# SeismicPi.net
KiCad netlist of a schematic drawn in EAGLE
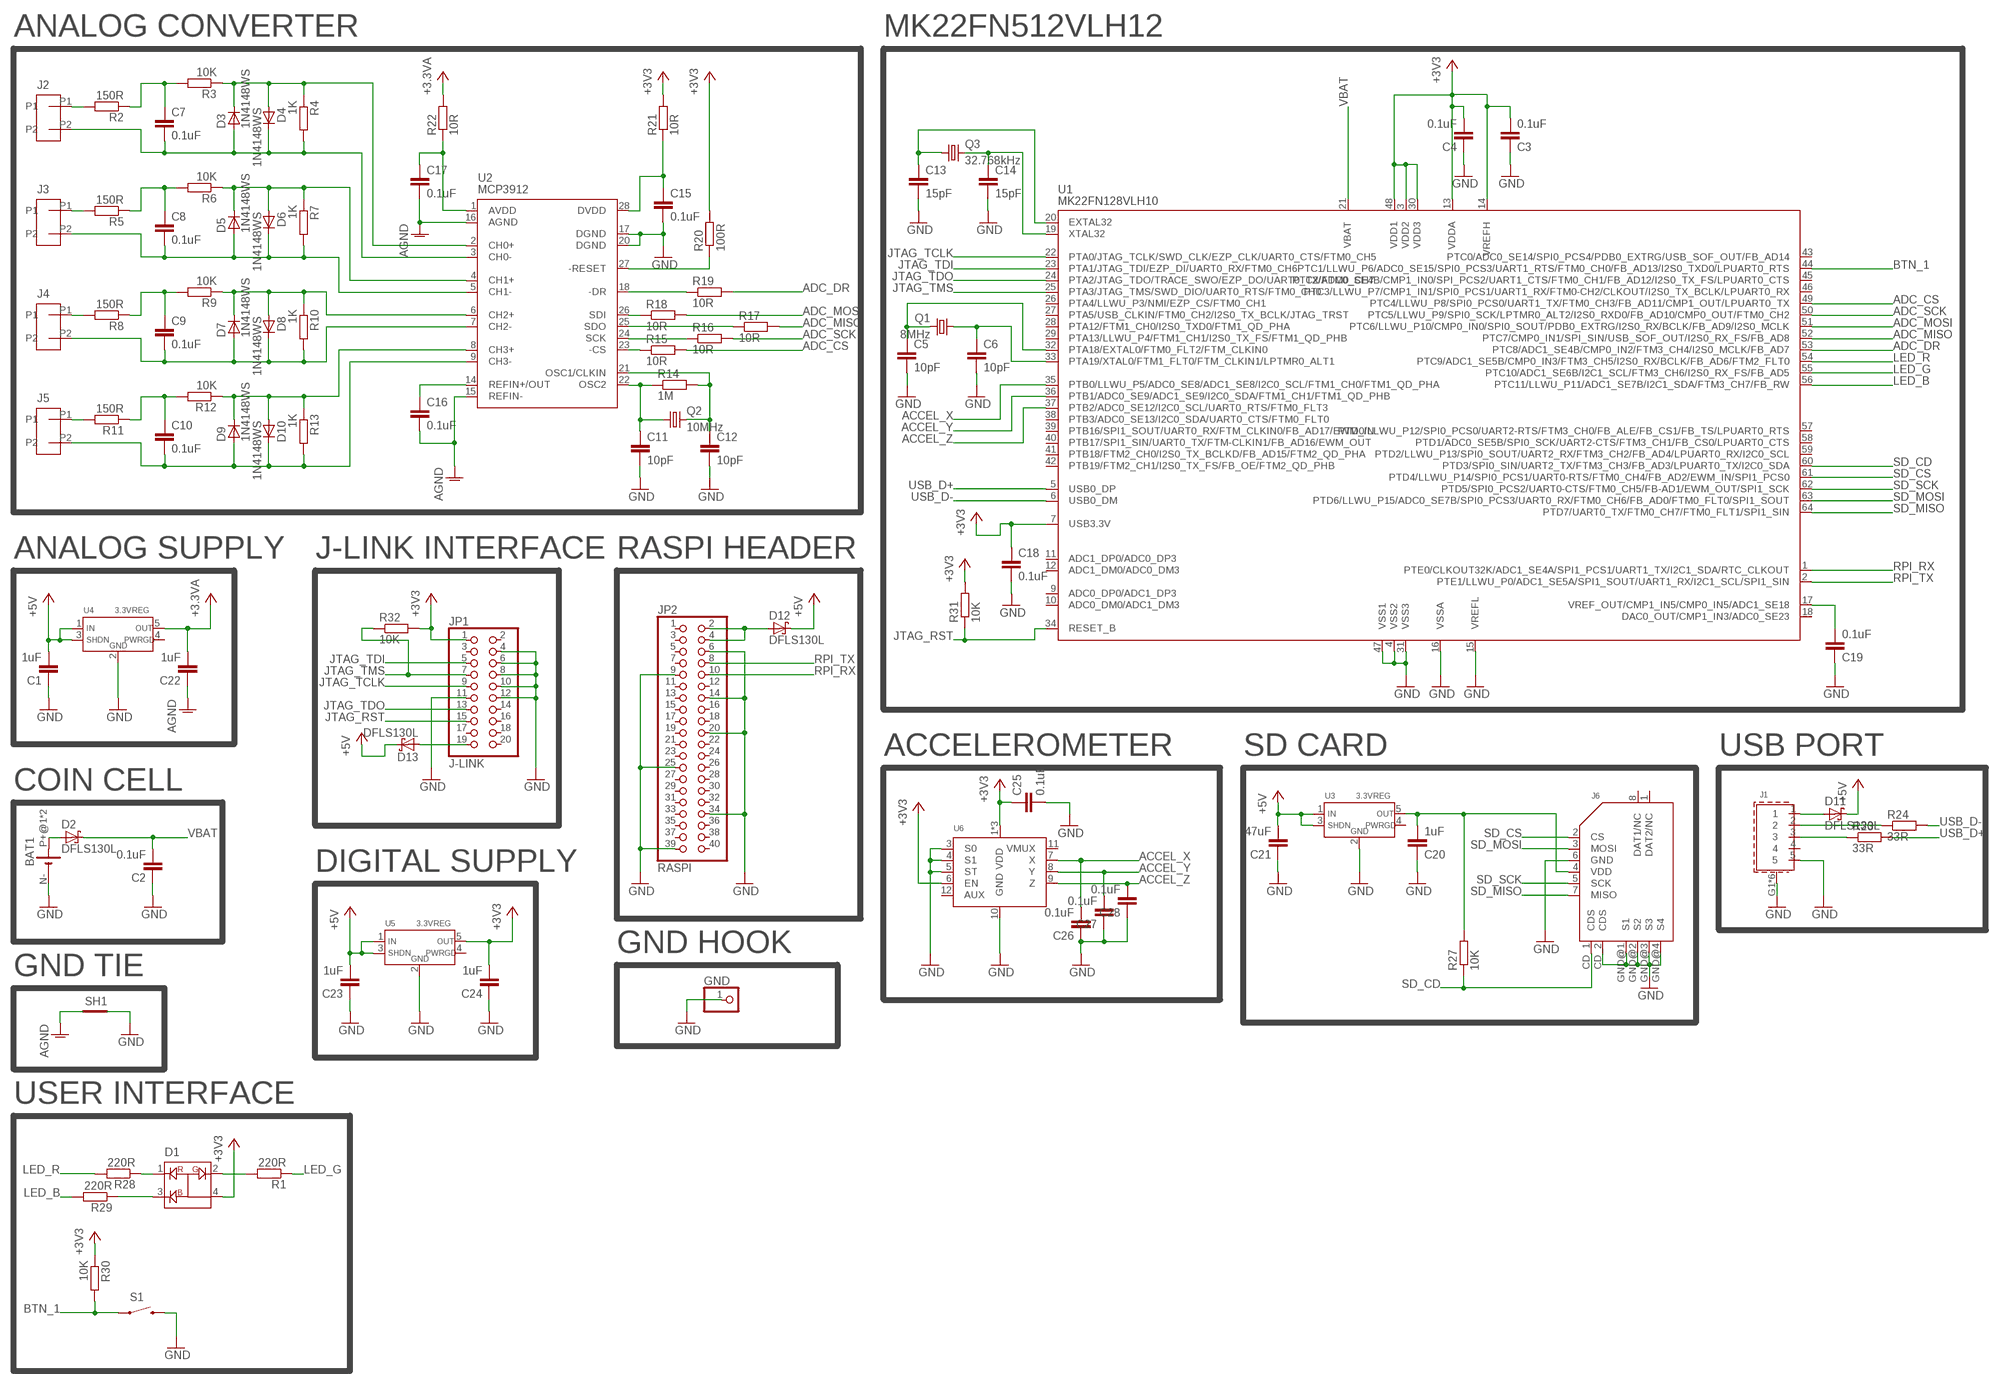
[diagram p0: schematic, sheet 1]

(export (version "E")
  (design (tool "Eeschema 10.0.6"))
  (components
    (comp (ref "BAT1")
      (value "BATTERY-HOLDER_11.6MM")
      (footprint "eagle-import:CELL_RETAINER_11.6MM")
      (fields (field (name "MF") "KEYSTONE") (field (name "MPN") "2997"))
      (libsource (lib "eagle-import") (part "BATTERY-HOLDER_11.6MM"))
    )
    (comp (ref "C1")
      (value "1uF")
      (footprint "eagle-import:C2012")
      (libsource (lib "eagle-import") (part "C-EUC2012"))
    )
    (comp (ref "C2")
      (value "0.1uF")
      (footprint "eagle-import:C2012")
      (libsource (lib "eagle-import") (part "C-EUC2012"))
    )
    (comp (ref "C3")
      (value "0.1uF")
      (footprint "eagle-import:C2012")
      (libsource (lib "eagle-import") (part "C-EUC2012"))
    )
    (comp (ref "C4")
      (value "0.1uF")
      (footprint "eagle-import:C2012")
      (libsource (lib "eagle-import") (part "C-EUC2012"))
    )
    (comp (ref "C5")
      (value "10pF")
      (footprint "eagle-import:C2012")
      (libsource (lib "eagle-import") (part "C-EUC2012"))
    )
    (comp (ref "C6")
      (value "10pF")
      (footprint "eagle-import:C2012")
      (libsource (lib "eagle-import") (part "C-EUC2012"))
    )
    (comp (ref "C7")
      (value "0.1uF")
      (footprint "eagle-import:C2012")
      (libsource (lib "eagle-import") (part "C-EUC2012"))
    )
    (comp (ref "C8")
      (value "0.1uF")
      (footprint "eagle-import:C2012")
      (libsource (lib "eagle-import") (part "C-EUC2012"))
    )
    (comp (ref "C9")
      (value "0.1uF")
      (footprint "eagle-import:C2012")
      (libsource (lib "eagle-import") (part "C-EUC2012"))
    )
    (comp (ref "C10")
      (value "0.1uF")
      (footprint "eagle-import:C2012")
      (libsource (lib "eagle-import") (part "C-EUC2012"))
    )
    (comp (ref "C11")
      (value "10pF")
      (footprint "eagle-import:C2012")
      (libsource (lib "eagle-import") (part "C-EUC2012"))
    )
    (comp (ref "C12")
      (value "10pF")
      (footprint "eagle-import:C2012")
      (libsource (lib "eagle-import") (part "C-EUC2012"))
    )
    (comp (ref "C13")
      (value "15pF")
      (footprint "eagle-import:C2012")
      (libsource (lib "eagle-import") (part "C-EUC2012"))
    )
    (comp (ref "C14")
      (value "15pF")
      (footprint "eagle-import:C2012")
      (libsource (lib "eagle-import") (part "C-EUC2012"))
    )
    (comp (ref "C15")
      (value "0.1uF")
      (footprint "eagle-import:C2012")
      (libsource (lib "eagle-import") (part "C-EUC2012"))
    )
    (comp (ref "C16")
      (value "0.1uF")
      (footprint "eagle-import:C2012")
      (libsource (lib "eagle-import") (part "C-EUC2012"))
    )
    (comp (ref "C17")
      (value "0.1uF")
      (footprint "eagle-import:C2012")
      (libsource (lib "eagle-import") (part "C-EUC2012"))
    )
    (comp (ref "C18")
      (value "0.1uF")
      (footprint "eagle-import:C2012")
      (libsource (lib "eagle-import") (part "C-EUC2012"))
    )
    (comp (ref "C19")
      (value "0.1uF")
      (footprint "eagle-import:C2012")
      (libsource (lib "eagle-import") (part "C-EUC2012"))
    )
    (comp (ref "C20")
      (value "1uF")
      (footprint "eagle-import:C2012")
      (libsource (lib "eagle-import") (part "C-EUC2012"))
    )
    (comp (ref "C21")
      (value "47uF")
      (footprint "eagle-import:C2012")
      (libsource (lib "eagle-import") (part "C-EUC2012"))
    )
    (comp (ref "C22")
      (value "1uF")
      (footprint "eagle-import:C2012")
      (libsource (lib "eagle-import") (part "C-EUC2012"))
    )
    (comp (ref "C23")
      (value "1uF")
      (footprint "eagle-import:C2012")
      (libsource (lib "eagle-import") (part "C-EUC2012"))
    )
    (comp (ref "C24")
      (value "1uF")
      (footprint "eagle-import:C2012")
      (libsource (lib "eagle-import") (part "C-EUC2012"))
    )
    (comp (ref "C25")
      (value "0.1uF")
      (footprint "eagle-import:C2012")
      (libsource (lib "eagle-import") (part "C-EUC2012"))
    )
    (comp (ref "C26")
      (value "0.1uF")
      (footprint "eagle-import:C2012")
      (libsource (lib "eagle-import") (part "C-EUC2012"))
    )
    (comp (ref "C27")
      (value "0.1uF")
      (footprint "eagle-import:C2012")
      (libsource (lib "eagle-import") (part "C-EUC2012"))
    )
    (comp (ref "C28")
      (value "0.1uF")
      (footprint "eagle-import:C2012")
      (libsource (lib "eagle-import") (part "C-EUC2012"))
    )
    (comp (ref "D1")
      (value "RGB-LED")
      (footprint "eagle-import:P-LCC4-0")
      (libsource (lib "eagle-import") (part "RGB-LED"))
    )
    (comp (ref "D2")
      (value "DFLS130L")
      (footprint "eagle-import:POWERDI323")
      (libsource (lib "eagle-import") (part "DFLS130L"))
    )
    (comp (ref "D3")
      (value "1N4148WS")
      (footprint "eagle-import:SOD323")
      (libsource (lib "eagle-import") (part "1N4148WS"))
    )
    (comp (ref "D4")
      (value "1N4148WS")
      (footprint "eagle-import:SOD323")
      (libsource (lib "eagle-import") (part "1N4148WS"))
    )
    (comp (ref "D5")
      (value "1N4148WS")
      (footprint "eagle-import:SOD323")
      (libsource (lib "eagle-import") (part "1N4148WS"))
    )
    (comp (ref "D6")
      (value "1N4148WS")
      (footprint "eagle-import:SOD323")
      (libsource (lib "eagle-import") (part "1N4148WS"))
    )
    (comp (ref "D7")
      (value "1N4148WS")
      (footprint "eagle-import:SOD323")
      (libsource (lib "eagle-import") (part "1N4148WS"))
    )
    (comp (ref "D8")
      (value "1N4148WS")
      (footprint "eagle-import:SOD323")
      (libsource (lib "eagle-import") (part "1N4148WS"))
    )
    (comp (ref "D9")
      (value "1N4148WS")
      (footprint "eagle-import:SOD323")
      (libsource (lib "eagle-import") (part "1N4148WS"))
    )
    (comp (ref "D10")
      (value "1N4148WS")
      (footprint "eagle-import:SOD323")
      (libsource (lib "eagle-import") (part "1N4148WS"))
    )
    (comp (ref "D11")
      (value "DFLS130L")
      (footprint "eagle-import:POWERDI323")
      (libsource (lib "eagle-import") (part "DFLS130L"))
    )
    (comp (ref "D12")
      (value "DFLS130L")
      (footprint "eagle-import:POWERDI323")
      (libsource (lib "eagle-import") (part "DFLS130L"))
    )
    (comp (ref "D13")
      (value "DFLS130L")
      (footprint "eagle-import:POWERDI323")
      (libsource (lib "eagle-import") (part "DFLS130L"))
    )
    (comp (ref "GND")
      (value "PINHD-1X1")
      (footprint "eagle-import:1X01")
      (libsource (lib "eagle-import") (part "PINHD-1X1"))
    )
    (comp (ref "J1")
      (value "USB-CONNMICRO")
      (footprint "eagle-import:MICRO-USB")
      (libsource (lib "eagle-import") (part "USB-CONNMICRO"))
    )
    (comp (ref "J2")
      (value "2WAY-TERMINAL")
      (footprint "eagle-import:2WAY-5.08")
      (libsource (lib "eagle-import") (part "2WAY-TERMINAL"))
    )
    (comp (ref "J3")
      (value "2WAY-TERMINAL")
      (footprint "eagle-import:2WAY-5.08")
      (libsource (lib "eagle-import") (part "2WAY-TERMINAL"))
    )
    (comp (ref "J4")
      (value "2WAY-TERMINAL")
      (footprint "eagle-import:2WAY-5.08")
      (libsource (lib "eagle-import") (part "2WAY-TERMINAL"))
    )
    (comp (ref "J5")
      (value "2WAY-TERMINAL")
      (footprint "eagle-import:2WAY-5.08")
      (libsource (lib "eagle-import") (part "2WAY-TERMINAL"))
    )
    (comp (ref "J6")
      (value "MICRO-SD")
      (footprint "eagle-import:MICRO-SD")
      (libsource (lib "eagle-import") (part "MICRO-SD"))
    )
    (comp (ref "JP1")
      (value "J-LINK")
      (footprint "eagle-import:2X10")
      (libsource (lib "eagle-import") (part "PINHD-2X10"))
    )
    (comp (ref "JP2")
      (value "RASPI")
      (footprint "eagle-import:2X20")
      (libsource (lib "eagle-import") (part "PINHD-2X20"))
    )
    (comp (ref "Q1")
      (value "8MHz")
      (footprint "eagle-import:ABM3B")
      (libsource (lib "eagle-import") (part "CRYSTAL"))
    )
    (comp (ref "Q2")
      (value "10MHz")
      (footprint "eagle-import:ABM3B")
      (libsource (lib "eagle-import") (part "CRYSTAL"))
    )
    (comp (ref "Q3")
      (value "32.768kHz")
      (footprint "eagle-import:MM20SS")
      (libsource (lib "eagle-import") (part "CRYSTALMM20SS"))
    )
    (comp (ref "R1")
      (value "220R")
      (footprint "eagle-import:M2012")
      (libsource (lib "eagle-import") (part "R-EU_M2012"))
    )
    (comp (ref "R2")
      (value "150R")
      (footprint "eagle-import:M2012")
      (libsource (lib "eagle-import") (part "R-EU_M2012"))
    )
    (comp (ref "R3")
      (value "10K")
      (footprint "eagle-import:M2012")
      (libsource (lib "eagle-import") (part "R-EU_M2012"))
    )
    (comp (ref "R4")
      (value "1K")
      (footprint "eagle-import:M2012")
      (libsource (lib "eagle-import") (part "R-EU_M2012"))
    )
    (comp (ref "R5")
      (value "150R")
      (footprint "eagle-import:M2012")
      (libsource (lib "eagle-import") (part "R-EU_M2012"))
    )
    (comp (ref "R6")
      (value "10K")
      (footprint "eagle-import:M2012")
      (libsource (lib "eagle-import") (part "R-EU_M2012"))
    )
    (comp (ref "R7")
      (value "1K")
      (footprint "eagle-import:M2012")
      (libsource (lib "eagle-import") (part "R-EU_M2012"))
    )
    (comp (ref "R8")
      (value "150R")
      (footprint "eagle-import:M2012")
      (libsource (lib "eagle-import") (part "R-EU_M2012"))
    )
    (comp (ref "R9")
      (value "10K")
      (footprint "eagle-import:M2012")
      (libsource (lib "eagle-import") (part "R-EU_M2012"))
    )
    (comp (ref "R10")
      (value "1K")
      (footprint "eagle-import:M2012")
      (libsource (lib "eagle-import") (part "R-EU_M2012"))
    )
    (comp (ref "R11")
      (value "150R")
      (footprint "eagle-import:M2012")
      (libsource (lib "eagle-import") (part "R-EU_M2012"))
    )
    (comp (ref "R12")
      (value "10K")
      (footprint "eagle-import:M2012")
      (libsource (lib "eagle-import") (part "R-EU_M2012"))
    )
    (comp (ref "R13")
      (value "1K")
      (footprint "eagle-import:M2012")
      (libsource (lib "eagle-import") (part "R-EU_M2012"))
    )
    (comp (ref "R14")
      (value "1M")
      (footprint "eagle-import:M2012")
      (libsource (lib "eagle-import") (part "R-EU_M2012"))
    )
    (comp (ref "R15")
      (value "10R")
      (footprint "eagle-import:M2012")
      (libsource (lib "eagle-import") (part "R-EU_M2012"))
    )
    (comp (ref "R16")
      (value "10R")
      (footprint "eagle-import:M2012")
      (libsource (lib "eagle-import") (part "R-EU_M2012"))
    )
    (comp (ref "R17")
      (value "10R")
      (footprint "eagle-import:M2012")
      (libsource (lib "eagle-import") (part "R-EU_M2012"))
    )
    (comp (ref "R18")
      (value "10R")
      (footprint "eagle-import:M2012")
      (libsource (lib "eagle-import") (part "R-EU_M2012"))
    )
    (comp (ref "R19")
      (value "10R")
      (footprint "eagle-import:M2012")
      (libsource (lib "eagle-import") (part "R-EU_M2012"))
    )
    (comp (ref "R20")
      (value "100R")
      (footprint "eagle-import:M2012")
      (libsource (lib "eagle-import") (part "R-EU_M2012"))
    )
    (comp (ref "R21")
      (value "10R")
      (footprint "eagle-import:M2012")
      (libsource (lib "eagle-import") (part "R-EU_M2012"))
    )
    (comp (ref "R22")
      (value "10R")
      (footprint "eagle-import:M2012")
      (libsource (lib "eagle-import") (part "R-EU_M2012"))
    )
    (comp (ref "R23")
      (value "33R")
      (footprint "eagle-import:M2012")
      (libsource (lib "eagle-import") (part "R-EU_M2012"))
    )
    (comp (ref "R24")
      (value "33R")
      (footprint "eagle-import:M2012")
      (libsource (lib "eagle-import") (part "R-EU_M2012"))
    )
    (comp (ref "R27")
      (value "10K")
      (footprint "eagle-import:M2012")
      (libsource (lib "eagle-import") (part "R-EU_M2012"))
    )
    (comp (ref "R28")
      (value "220R")
      (footprint "eagle-import:M2012")
      (libsource (lib "eagle-import") (part "R-EU_M2012"))
    )
    (comp (ref "R29")
      (value "220R")
      (footprint "eagle-import:M2012")
      (libsource (lib "eagle-import") (part "R-EU_M2012"))
    )
    (comp (ref "R30")
      (value "10K")
      (footprint "eagle-import:M2012")
      (libsource (lib "eagle-import") (part "R-EU_M2012"))
    )
    (comp (ref "R31")
      (value "10K")
      (footprint "eagle-import:M2012")
      (libsource (lib "eagle-import") (part "R-EU_M2012"))
    )
    (comp (ref "R32")
      (value "10K")
      (footprint "eagle-import:M2012")
      (libsource (lib "eagle-import") (part "R-EU_M2012"))
    )
    (comp (ref "S1")
      (value "SWITCH-MOMENTARY-2PTH")
      (footprint "eagle-import:TACTILE-PTH")
      (libsource (lib "eagle-import") (part "SWITCH-MOMENTARY-2PTH"))
    )
    (comp (ref "SH1")
      (value "SHORT-HT5")
      (footprint "eagle-import:SHORT_TOP-50")
      (libsource (lib "eagle-import") (part "SHORT-HT5"))
    )
    (comp (ref "U1")
      (value "MK22FN128VLH10")
      (footprint "eagle-import:LQFP-64_10X10X1.6")
      (libsource (lib "eagle-import") (part "MK22FN128VLH10"))
    )
    (comp (ref "U2")
      (value "MCP3912")
      (footprint "eagle-import:SSOP28")
      (libsource (lib "eagle-import") (part "MCP3912"))
    )
    (comp (ref "U3")
      (value "3.3VREG")
      (footprint "eagle-import:SOT23-5")
      (libsource (lib "eagle-import") (part "3.3VREG"))
    )
    (comp (ref "U4")
      (value "3.3VREG")
      (footprint "eagle-import:SOT23-5")
      (libsource (lib "eagle-import") (part "3.3VREG"))
    )
    (comp (ref "U5")
      (value "3.3VREG")
      (footprint "eagle-import:SOT23-5")
      (libsource (lib "eagle-import") (part "3.3VREG"))
    )
    (comp (ref "U6")
      (value "KXRB5-2050")
      (footprint "eagle-import:LGA-14")
      (libsource (lib "eagle-import") (part "KXRB5-2050"))
    )
  )
  (nets
    (net (code "1") (name "+3.3VA") (class "Default")
      (node (ref "C22") (pin "2") (pinfunction "2_2") (pintype "passive"))
      (node (ref "R22") (pin "2") (pinfunction "2_2") (pintype "passive"))
      (node (ref "U4") (pin "5") (pinfunction "OUT_5") (pintype "bidirectional"))
    )
    (net (code "2") (name "+3V3") (class "Default")
      (node (ref "C18") (pin "1") (pinfunction "1_1") (pintype "passive"))
      (node (ref "C24") (pin "2") (pinfunction "2_2") (pintype "passive"))
      (node (ref "C25") (pin "1") (pinfunction "1_1") (pintype "passive"))
      (node (ref "C3") (pin "2") (pinfunction "2_2") (pintype "passive"))
      (node (ref "C4") (pin "2") (pinfunction "2_2") (pintype "passive"))
      (node (ref "D1") (pin "4") (pinfunction "AN_4") (pintype "bidirectional"))
      (node (ref "JP1") (pin "1") (pinfunction "1_1") (pintype "passive"))
      (node (ref "R20") (pin "2") (pinfunction "2_2") (pintype "passive"))
      (node (ref "R21") (pin "2") (pinfunction "2_2") (pintype "passive"))
      (node (ref "R30") (pin "1") (pinfunction "1_1") (pintype "passive"))
      (node (ref "R31") (pin "2") (pinfunction "2_2") (pintype "passive"))
      (node (ref "R32") (pin "2") (pinfunction "2_2") (pintype "passive"))
      (node (ref "U1") (pin "13") (pinfunction "VDDA_13") (pintype "power_in"))
      (node (ref "U1") (pin "14") (pinfunction "VREFH_14") (pintype "power_in"))
      (node (ref "U1") (pin "3") (pinfunction "VDD2_3") (pintype "power_in"))
      (node (ref "U1") (pin "30") (pinfunction "VDD3_30") (pintype "power_in"))
      (node (ref "U1") (pin "48") (pinfunction "VDD1_48") (pintype "power_in"))
      (node (ref "U1") (pin "7") (pinfunction "USB3.3V_7") (pintype "input"))
      (node (ref "U5") (pin "5") (pinfunction "OUT_5") (pintype "bidirectional"))
      (node (ref "U6") (pin "1") (pinfunction "VDD_1") (pintype "bidirectional"))
      (node (ref "U6") (pin "13") (pinfunction "VDD_13") (pintype "bidirectional"))
      (node (ref "U6") (pin "14") (pinfunction "VDD_14") (pintype "bidirectional"))
      (node (ref "U6") (pin "6") (pinfunction "EN_6") (pintype "bidirectional"))
    )
    (net (code "3") (name "+5V") (class "Default")
      (node (ref "C1") (pin "2") (pinfunction "2_2") (pintype "passive"))
      (node (ref "C21") (pin "2") (pinfunction "2_2") (pintype "passive"))
      (node (ref "C23") (pin "2") (pinfunction "2_2") (pintype "passive"))
      (node (ref "D11") (pin "C") (pinfunction "C_C") (pintype "passive"))
      (node (ref "D12") (pin "C") (pinfunction "C_C") (pintype "passive"))
      (node (ref "D13") (pin "C") (pinfunction "C_C") (pintype "passive"))
      (node (ref "U3") (pin "1") (pinfunction "IN_1") (pintype "bidirectional"))
      (node (ref "U3") (pin "3") (pinfunction "SHDN_3") (pintype "bidirectional"))
      (node (ref "U4") (pin "1") (pinfunction "IN_1") (pintype "bidirectional"))
      (node (ref "U4") (pin "3") (pinfunction "SHDN_3") (pintype "bidirectional"))
      (node (ref "U5") (pin "1") (pinfunction "IN_1") (pintype "bidirectional"))
      (node (ref "U5") (pin "3") (pinfunction "SHDN_3") (pintype "bidirectional"))
    )
    (net (code "4") (name "/ACCEL_X") (class "Default")
      (node (ref "C26") (pin "2") (pinfunction "2_2") (pintype "passive"))
      (node (ref "U1") (pin "35") (pinfunction "PTB0/LLWU_P5/ADC0_SE8/ADC1_SE8/I2C0_SCL/FTM1_CH0/FTM1_QD_PHA_35") (pintype "bidirectional"))
      (node (ref "U6") (pin "7") (pinfunction "X_7") (pintype "bidirectional"))
    )
    (net (code "5") (name "/ACCEL_Y") (class "Default")
      (node (ref "C27") (pin "2") (pinfunction "2_2") (pintype "passive"))
      (node (ref "U1") (pin "36") (pinfunction "PTB1/ADC0_SE9/ADC1_SE9/I2C0_SDA/FTM1_CH1/FTM1_QD_PHB_36") (pintype "bidirectional"))
      (node (ref "U6") (pin "8") (pinfunction "Y_8") (pintype "bidirectional"))
    )
    (net (code "6") (name "/ACCEL_Z") (class "Default")
      (node (ref "C28") (pin "2") (pinfunction "2_2") (pintype "passive"))
      (node (ref "U1") (pin "37") (pinfunction "PTB2/ADC0_SE12/I2C0_SCL/UART0_RTS/FTM0_FLT3_37") (pintype "bidirectional"))
      (node (ref "U6") (pin "9") (pinfunction "Z_9") (pintype "bidirectional"))
    )
    (net (code "7") (name "/ADC_CS") (class "Default")
      (node (ref "R15") (pin "2") (pinfunction "2_2") (pintype "passive"))
      (node (ref "U1") (pin "49") (pinfunction "PTC4/LLWU_P8/SPI0_PCS0/UART1_TX/FTM0_CH3/FB_AD11/CMP1_OUT/LPUART0_TX_49") (pintype "bidirectional"))
    )
    (net (code "8") (name "/ADC_DR") (class "Default")
      (node (ref "R19") (pin "2") (pinfunction "2_2") (pintype "passive"))
      (node (ref "U1") (pin "53") (pinfunction "PTC8/ADC1_SE4B/CMP0_IN2/FTM3_CH4/I2S0_MCLK/FB_AD7_53") (pintype "bidirectional"))
    )
    (net (code "9") (name "/ADC_MISO") (class "Default")
      (node (ref "R17") (pin "2") (pinfunction "2_2") (pintype "passive"))
      (node (ref "U1") (pin "52") (pinfunction "PTC7/CMP0_IN1/SPI_SIN/USB_SOF_OUT/I2S0_RX_FS/FB_AD8_52") (pintype "bidirectional"))
    )
    (net (code "10") (name "/ADC_MOSI") (class "Default")
      (node (ref "R18") (pin "2") (pinfunction "2_2") (pintype "passive"))
      (node (ref "U1") (pin "51") (pinfunction "PTC6/LLWU_P10/CMP0_IN0/SPI0_SOUT/PDB0_EXTRG/I2S0_RX/BCLK/FB_AD9/I2S0_MCLK_51") (pintype "bidirectional"))
    )
    (net (code "11") (name "/ADC_SCK") (class "Default")
      (node (ref "R16") (pin "2") (pinfunction "2_2") (pintype "passive"))
      (node (ref "U1") (pin "50") (pinfunction "PTC5/LLWU_P9/SPI0_SCK/LPTMR0_ALT2/I2S0_RXD0/FB_AD10/CMP0_OUT/FTM0_CH2_50") (pintype "bidirectional"))
    )
    (net (code "12") (name "/BTN_1") (class "Default")
      (node (ref "R30") (pin "2") (pinfunction "2_2") (pintype "passive"))
      (node (ref "S1") (pin "1") (pinfunction "1_1") (pintype "passive"))
      (node (ref "U1") (pin "44") (pinfunction "PTC1/LLWU_P6/ADC0_SE15/SPI0_PCS3/UART1_RTS/FTM0_CH0/FB_AD13/I2S0_TXD0/LPUART0_RTS_44") (pintype "bidirectional"))
    )
    (net (code "13") (name "/JTAG_RST") (class "Default")
      (node (ref "JP1") (pin "15") (pinfunction "15_15") (pintype "passive"))
      (node (ref "R31") (pin "1") (pinfunction "1_1") (pintype "passive"))
      (node (ref "U1") (pin "34") (pinfunction "RESET_B_34") (pintype "passive"))
    )
    (net (code "14") (name "/JTAG_TCLK") (class "Default")
      (node (ref "JP1") (pin "9") (pinfunction "9_9") (pintype "passive"))
      (node (ref "U1") (pin "22") (pinfunction "PTA0/JTAG_TCLK/SWD_CLK/EZP_CLK/UART0_CTS/FTM0_CH5_22") (pintype "bidirectional"))
    )
    (net (code "15") (name "/JTAG_TDI") (class "Default")
      (node (ref "JP1") (pin "5") (pinfunction "5_5") (pintype "passive"))
      (node (ref "U1") (pin "23") (pinfunction "PTA1/JTAG_TDI/EZP_DI/UART0_RX/FTM0_CH6_23") (pintype "bidirectional"))
    )
    (net (code "16") (name "/JTAG_TDO") (class "Default")
      (node (ref "JP1") (pin "13") (pinfunction "13_13") (pintype "passive"))
      (node (ref "U1") (pin "24") (pinfunction "PTA2/JTAG_TDO/TRACE_SWO/EZP_DO/UART0_TX/FTM0_CH7_24") (pintype "bidirectional"))
    )
    (net (code "17") (name "/JTAG_TMS") (class "Default")
      (node (ref "JP1") (pin "7") (pinfunction "7_7") (pintype "passive"))
      (node (ref "R32") (pin "1") (pinfunction "1_1") (pintype "passive"))
      (node (ref "U1") (pin "25") (pinfunction "PTA3/JTAG_TMS/SWD_DIO/UART0_RTS/FTM0_CH0_25") (pintype "bidirectional"))
    )
    (net (code "18") (name "/LED_B") (class "Default")
      (node (ref "R29") (pin "2") (pinfunction "2_2") (pintype "passive"))
      (node (ref "U1") (pin "56") (pinfunction "PTC11/LLWU_P11/ADC1_SE7B/I2C1_SDA/FTM3_CH7/FB_RW_56") (pintype "bidirectional"))
    )
    (net (code "19") (name "/LED_G") (class "Default")
      (node (ref "R1") (pin "1") (pinfunction "1_1") (pintype "passive"))
      (node (ref "U1") (pin "55") (pinfunction "PTC10/ADC1_SE6B/I2C1_SCL/FTM3_CH6/I2S0_RX_FS/FB_AD5_55") (pintype "bidirectional"))
    )
    (net (code "20") (name "/LED_R") (class "Default")
      (node (ref "R28") (pin "2") (pinfunction "2_2") (pintype "passive"))
      (node (ref "U1") (pin "54") (pinfunction "PTC9/ADC1_SE5B/CMP0_IN3/FTM3_CH5/I2S0_RX/BCLK/FB_AD6/FTM2_FLT0_54") (pintype "bidirectional"))
    )
    (net (code "21") (name "/RPI_RX") (class "Default")
      (node (ref "JP2") (pin "10") (pinfunction "10_10") (pintype "passive"))
      (node (ref "U1") (pin "1") (pinfunction "PTE0/CLKOUT32K/ADC1_SE4A/SPI1_PCS1/UART1_TX/I2C1_SDA/RTC_CLKOUT_1") (pintype "bidirectional"))
    )
    (net (code "22") (name "/RPI_TX") (class "Default")
      (node (ref "JP2") (pin "8") (pinfunction "8_8") (pintype "passive"))
      (node (ref "U1") (pin "2") (pinfunction "PTE1/LLWU_P0/ADC1_SE5A/SPI1_SOUT/UART1_RX/I2C1_SCL/SPI1_SIN_2") (pintype "bidirectional"))
    )
    (net (code "23") (name "/SD_CD") (class "Default")
      (node (ref "J6") (pin "CD_1") (pinfunction "CDS_CD_1") (pintype "bidirectional"))
      (node (ref "R27") (pin "1") (pinfunction "1_1") (pintype "passive"))
      (node (ref "U1") (pin "60") (pinfunction "PTD3/SPI0_SIN/UART2_TX/FTM3_CH3/FB_AD3/LPUART0_TX/I2C0_SDA_60") (pintype "bidirectional"))
    )
    (net (code "24") (name "/SD_CS") (class "Default")
      (node (ref "J6") (pin "2") (pinfunction "CS_2") (pintype "bidirectional"))
      (node (ref "U1") (pin "61") (pinfunction "PTD4/LLWU_P14/SPI0_PCS1/UART0-RTS/FTM0_CH4/FB_AD2/EWM_IN/SPI1_PCS0_61") (pintype "bidirectional"))
    )
    (net (code "25") (name "/SD_MISO") (class "Default")
      (node (ref "J6") (pin "7") (pinfunction "MISO_7") (pintype "bidirectional"))
      (node (ref "U1") (pin "64") (pinfunction "PTD7/UART0_TX/FTM0_CH7/FTM0_FLT1/SPI1_SIN_64") (pintype "bidirectional"))
    )
    (net (code "26") (name "/SD_MOSI") (class "Default")
      (node (ref "J6") (pin "3") (pinfunction "MOSI_3") (pintype "bidirectional"))
      (node (ref "U1") (pin "63") (pinfunction "PTD6/LLWU_P15/ADC0_SE7B/SPI0_PCS3/UART0_RX/FTM0_CH6/FB_AD0/FTM0_FLT0/SPI1_SOUT_63") (pintype "bidirectional"))
    )
    (net (code "27") (name "/SD_SCK") (class "Default")
      (node (ref "J6") (pin "5") (pinfunction "SCK_5") (pintype "bidirectional"))
      (node (ref "U1") (pin "62") (pinfunction "PTD5/SPI0_PCS2/UART0-CTS/FTM0_CH5/FB-AD1/EWM_OUT/SPI1_SCK_62") (pintype "bidirectional"))
    )
    (net (code "28") (name "/USB_D+") (class "Default")
      (node (ref "R23") (pin "2") (pinfunction "2_2") (pintype "passive"))
      (node (ref "U1") (pin "5") (pinfunction "USB0_DP_5") (pintype "passive"))
    )
    (net (code "29") (name "/USB_D-") (class "Default")
      (node (ref "R24") (pin "2") (pinfunction "2_2") (pintype "passive"))
      (node (ref "U1") (pin "6") (pinfunction "USB0_DM_6") (pintype "passive"))
    )
    (net (code "30") (name "/VBAT") (class "Default")
      (node (ref "C2") (pin "2") (pinfunction "2_2") (pintype "passive"))
      (node (ref "D2") (pin "C") (pinfunction "C_C") (pintype "passive"))
      (node (ref "U1") (pin "21") (pinfunction "VBAT_21") (pintype "power_in"))
    )
    (net (code "31") (name "AGND") (class "Default")
      (node (ref "C16") (pin "2") (pinfunction "2_2") (pintype "passive"))
      (node (ref "C17") (pin "2") (pinfunction "2_2") (pintype "passive"))
      (node (ref "C22") (pin "1") (pinfunction "1_1") (pintype "passive"))
      (node (ref "SH1") (pin "1") (pinfunction "P$1_1") (pintype "bidirectional"))
      (node (ref "U2") (pin "15") (pinfunction "REFIN-_15") (pintype "bidirectional"))
      (node (ref "U2") (pin "16") (pinfunction "AGND_16") (pintype "bidirectional"))
    )
    (net (code "32") (name "GND") (class "Default")
      (node (ref "BAT1") (pin "N-") (pinfunction "-_N-") (pintype "passive"))
      (node (ref "C1") (pin "1") (pinfunction "1_1") (pintype "passive"))
      (node (ref "C11") (pin "2") (pinfunction "2_2") (pintype "passive"))
      (node (ref "C12") (pin "2") (pinfunction "2_2") (pintype "passive"))
      (node (ref "C13") (pin "2") (pinfunction "2_2") (pintype "passive"))
      (node (ref "C14") (pin "2") (pinfunction "2_2") (pintype "passive"))
      (node (ref "C15") (pin "2") (pinfunction "2_2") (pintype "passive"))
      (node (ref "C18") (pin "2") (pinfunction "2_2") (pintype "passive"))
      (node (ref "C19") (pin "1") (pinfunction "1_1") (pintype "passive"))
      (node (ref "C2") (pin "1") (pinfunction "1_1") (pintype "passive"))
      (node (ref "C20") (pin "1") (pinfunction "1_1") (pintype "passive"))
      (node (ref "C21") (pin "1") (pinfunction "1_1") (pintype "passive"))
      (node (ref "C23") (pin "1") (pinfunction "1_1") (pintype "passive"))
      (node (ref "C24") (pin "1") (pinfunction "1_1") (pintype "passive"))
      (node (ref "C25") (pin "2") (pinfunction "2_2") (pintype "passive"))
      (node (ref "C26") (pin "1") (pinfunction "1_1") (pintype "passive"))
      (node (ref "C27") (pin "1") (pinfunction "1_1") (pintype "passive"))
      (node (ref "C28") (pin "1") (pinfunction "1_1") (pintype "passive"))
      (node (ref "C3") (pin "1") (pinfunction "1_1") (pintype "passive"))
      (node (ref "C4") (pin "1") (pinfunction "1_1") (pintype "passive"))
      (node (ref "C5") (pin "2") (pinfunction "2_2") (pintype "passive"))
      (node (ref "C6") (pin "2") (pinfunction "2_2") (pintype "passive"))
      (node (ref "GND") (pin "1") (pinfunction "1_1") (pintype "passive"))
      (node (ref "J1") (pin "5") (pinfunction "5_5") (pintype "bidirectional"))
      (node (ref "J1") (pin "G1") (pinfunction "GND_G1") (pintype "bidirectional"))
      (node (ref "J1") (pin "G2") (pinfunction "GND_G2") (pintype "bidirectional"))
      (node (ref "J1") (pin "G3") (pinfunction "GND_G3") (pintype "bidirectional"))
      (node (ref "J1") (pin "G4") (pinfunction "GND_G4") (pintype "bidirectional"))
      (node (ref "J1") (pin "G5") (pinfunction "GND_G5") (pintype "bidirectional"))
      (node (ref "J1") (pin "G6") (pinfunction "GND_G6") (pintype "bidirectional"))
      (node (ref "J6") (pin "6") (pinfunction "GND_6") (pintype "bidirectional"))
      (node (ref "J6") (pin "CD_2") (pinfunction "CDS_CD_2") (pintype "bidirectional"))
      (node (ref "J6") (pin "GND@1") (pinfunction "S1_GND@1") (pintype "bidirectional"))
      (node (ref "J6") (pin "GND@2") (pinfunction "S2_GND@2") (pintype "bidirectional"))
      (node (ref "J6") (pin "GND@3") (pinfunction "S3_GND@3") (pintype "bidirectional"))
      (node (ref "J6") (pin "GND@4") (pinfunction "S4_GND@4") (pintype "bidirectional"))
      (node (ref "JP1") (pin "10") (pinfunction "10_10") (pintype "passive"))
      (node (ref "JP1") (pin "11") (pinfunction "11_11") (pintype "passive"))
      (node (ref "JP1") (pin "12") (pinfunction "12_12") (pintype "passive"))
      (node (ref "JP1") (pin "4") (pinfunction "4_4") (pintype "passive"))
      (node (ref "JP1") (pin "6") (pinfunction "6_6") (pintype "passive"))
      (node (ref "JP1") (pin "8") (pinfunction "8_8") (pintype "passive"))
      (node (ref "JP2") (pin "14") (pinfunction "14_14") (pintype "passive"))
      (node (ref "JP2") (pin "20") (pinfunction "20_20") (pintype "passive"))
      (node (ref "JP2") (pin "25") (pinfunction "25_25") (pintype "passive"))
      (node (ref "JP2") (pin "34") (pinfunction "34_34") (pintype "passive"))
      (node (ref "JP2") (pin "39") (pinfunction "39_39") (pintype "passive"))
      (node (ref "JP2") (pin "6") (pinfunction "6_6") (pintype "passive"))
      (node (ref "JP2") (pin "9") (pinfunction "9_9") (pintype "passive"))
      (node (ref "S1") (pin "3") (pinfunction "2_3") (pintype "passive"))
      (node (ref "SH1") (pin "2") (pinfunction "P$2_2") (pintype "bidirectional"))
      (node (ref "U1") (pin "15") (pinfunction "VREFL_15") (pintype "power_in"))
      (node (ref "U1") (pin "16") (pinfunction "VSSA_16") (pintype "power_in"))
      (node (ref "U1") (pin "31") (pinfunction "VSS3_31") (pintype "power_in"))
      (node (ref "U1") (pin "4") (pinfunction "VSS2_4") (pintype "power_in"))
      (node (ref "U1") (pin "47") (pinfunction "VSS1_47") (pintype "power_in"))
      (node (ref "U2") (pin "17") (pinfunction "DGND_17") (pintype "bidirectional"))
      (node (ref "U2") (pin "20") (pinfunction "DGND_20") (pintype "bidirectional"))
      (node (ref "U3") (pin "2") (pinfunction "GND_2") (pintype "bidirectional"))
      (node (ref "U4") (pin "2") (pinfunction "GND_2") (pintype "bidirectional"))
      (node (ref "U5") (pin "2") (pinfunction "GND_2") (pintype "bidirectional"))
      (node (ref "U6") (pin "10") (pinfunction "GND_10") (pintype "bidirectional"))
      (node (ref "U6") (pin "3") (pinfunction "S0_3") (pintype "bidirectional"))
      (node (ref "U6") (pin "4") (pinfunction "S1_4") (pintype "bidirectional"))
      (node (ref "U6") (pin "5") (pinfunction "ST_5") (pintype "bidirectional"))
    )
    (net (code "33") (name "Net-(BAT1-+-PadP+@1)") (class "Default")
      (node (ref "BAT1") (pin "P+@1") (pinfunction "+_P+@1") (pintype "passive"))
      (node (ref "BAT1") (pin "P+@2") (pinfunction "+_P+@2") (pintype "passive"))
      (node (ref "D2") (pin "A") (pinfunction "A_A") (pintype "passive"))
    )
    (net (code "34") (name "Net-(C7-Pad1)") (class "Default")
      (node (ref "C7") (pin "1") (pinfunction "1_1") (pintype "passive"))
      (node (ref "R2") (pin "1") (pinfunction "1_1") (pintype "passive"))
      (node (ref "R3") (pin "2") (pinfunction "2_2") (pintype "passive"))
    )
    (net (code "35") (name "Net-(C8-Pad1)") (class "Default")
      (node (ref "C8") (pin "1") (pinfunction "1_1") (pintype "passive"))
      (node (ref "R5") (pin "1") (pinfunction "1_1") (pintype "passive"))
      (node (ref "R6") (pin "2") (pinfunction "2_2") (pintype "passive"))
    )
    (net (code "36") (name "Net-(C9-Pad1)") (class "Default")
      (node (ref "C9") (pin "1") (pinfunction "1_1") (pintype "passive"))
      (node (ref "R8") (pin "1") (pinfunction "1_1") (pintype "passive"))
      (node (ref "R9") (pin "2") (pinfunction "2_2") (pintype "passive"))
    )
    (net (code "37") (name "Net-(C10-Pad1)") (class "Default")
      (node (ref "C10") (pin "1") (pinfunction "1_1") (pintype "passive"))
      (node (ref "R11") (pin "1") (pinfunction "1_1") (pintype "passive"))
      (node (ref "R12") (pin "2") (pinfunction "2_2") (pintype "passive"))
    )
    (net (code "38") (name "Net-(D1-B)") (class "Default")
      (node (ref "D1") (pin "3") (pinfunction "B_3") (pintype "bidirectional"))
      (node (ref "R29") (pin "1") (pinfunction "1_1") (pintype "passive"))
    )
    (net (code "39") (name "Net-(D1-G)") (class "Default")
      (node (ref "D1") (pin "2") (pinfunction "G_2") (pintype "bidirectional"))
      (node (ref "R1") (pin "2") (pinfunction "2_2") (pintype "passive"))
    )
    (net (code "40") (name "Net-(D1-R)") (class "Default")
      (node (ref "D1") (pin "1") (pinfunction "R_1") (pintype "bidirectional"))
      (node (ref "R28") (pin "1") (pinfunction "1_1") (pintype "passive"))
    )
    (net (code "41") (name "Net-(D3-A)") (class "Default")
      (node (ref "C7") (pin "2") (pinfunction "2_2") (pintype "passive"))
      (node (ref "D3") (pin "2") (pinfunction "A_2") (pintype "passive"))
      (node (ref "D4") (pin "1") (pinfunction "C_1") (pintype "passive"))
      (node (ref "J2") (pin "P2") (pinfunction "P2_P2") (pintype "bidirectional"))
      (node (ref "R4") (pin "2") (pinfunction "2_2") (pintype "passive"))
      (node (ref "U2") (pin "3") (pinfunction "CH0-_3") (pintype "bidirectional"))
    )
    (net (code "42") (name "Net-(D3-C)") (class "Default")
      (node (ref "D3") (pin "1") (pinfunction "C_1") (pintype "passive"))
      (node (ref "D4") (pin "2") (pinfunction "A_2") (pintype "passive"))
      (node (ref "R3") (pin "1") (pinfunction "1_1") (pintype "passive"))
      (node (ref "R4") (pin "1") (pinfunction "1_1") (pintype "passive"))
      (node (ref "U2") (pin "2") (pinfunction "CH0+_2") (pintype "bidirectional"))
    )
    (net (code "43") (name "Net-(D5-A)") (class "Default")
      (node (ref "C8") (pin "2") (pinfunction "2_2") (pintype "passive"))
      (node (ref "D5") (pin "2") (pinfunction "A_2") (pintype "passive"))
      (node (ref "D6") (pin "1") (pinfunction "C_1") (pintype "passive"))
      (node (ref "J3") (pin "P2") (pinfunction "P2_P2") (pintype "bidirectional"))
      (node (ref "R7") (pin "2") (pinfunction "2_2") (pintype "passive"))
      (node (ref "U2") (pin "5") (pinfunction "CH1-_5") (pintype "bidirectional"))
    )
    (net (code "44") (name "Net-(D5-C)") (class "Default")
      (node (ref "D5") (pin "1") (pinfunction "C_1") (pintype "passive"))
      (node (ref "D6") (pin "2") (pinfunction "A_2") (pintype "passive"))
      (node (ref "R6") (pin "1") (pinfunction "1_1") (pintype "passive"))
      (node (ref "R7") (pin "1") (pinfunction "1_1") (pintype "passive"))
      (node (ref "U2") (pin "4") (pinfunction "CH1+_4") (pintype "bidirectional"))
    )
    (net (code "45") (name "Net-(D7-A)") (class "Default")
      (node (ref "C9") (pin "2") (pinfunction "2_2") (pintype "passive"))
      (node (ref "D7") (pin "2") (pinfunction "A_2") (pintype "passive"))
      (node (ref "D8") (pin "1") (pinfunction "C_1") (pintype "passive"))
      (node (ref "J4") (pin "P2") (pinfunction "P2_P2") (pintype "bidirectional"))
      (node (ref "R10") (pin "2") (pinfunction "2_2") (pintype "passive"))
      (node (ref "U2") (pin "7") (pinfunction "CH2-_7") (pintype "bidirectional"))
    )
    (net (code "46") (name "Net-(D7-C)") (class "Default")
      (node (ref "D7") (pin "1") (pinfunction "C_1") (pintype "passive"))
      (node (ref "D8") (pin "2") (pinfunction "A_2") (pintype "passive"))
      (node (ref "R10") (pin "1") (pinfunction "1_1") (pintype "passive"))
      (node (ref "R9") (pin "1") (pinfunction "1_1") (pintype "passive"))
      (node (ref "U2") (pin "6") (pinfunction "CH2+_6") (pintype "bidirectional"))
    )
    (net (code "47") (name "Net-(D10-A)") (class "Default")
      (node (ref "D10") (pin "2") (pinfunction "A_2") (pintype "passive"))
      (node (ref "D9") (pin "1") (pinfunction "C_1") (pintype "passive"))
      (node (ref "R12") (pin "1") (pinfunction "1_1") (pintype "passive"))
      (node (ref "R13") (pin "1") (pinfunction "1_1") (pintype "passive"))
      (node (ref "U2") (pin "8") (pinfunction "CH3+_8") (pintype "bidirectional"))
    )
    (net (code "48") (name "Net-(D10-C)") (class "Default")
      (node (ref "C10") (pin "2") (pinfunction "2_2") (pintype "passive"))
      (node (ref "D10") (pin "1") (pinfunction "C_1") (pintype "passive"))
      (node (ref "D9") (pin "2") (pinfunction "A_2") (pintype "passive"))
      (node (ref "J5") (pin "P2") (pinfunction "P2_P2") (pintype "bidirectional"))
      (node (ref "R13") (pin "2") (pinfunction "2_2") (pintype "passive"))
      (node (ref "U2") (pin "9") (pinfunction "CH3-_9") (pintype "bidirectional"))
    )
    (net (code "49") (name "Net-(D11-PadA)") (class "Default")
      (node (ref "D11") (pin "A") (pinfunction "A_A") (pintype "passive"))
      (node (ref "J1") (pin "1") (pinfunction "1_1") (pintype "bidirectional"))
    )
    (net (code "50") (name "Net-(D12-PadA)") (class "Default")
      (node (ref "D12") (pin "A") (pinfunction "A_A") (pintype "passive"))
      (node (ref "JP2") (pin "2") (pinfunction "2_2") (pintype "passive"))
      (node (ref "JP2") (pin "4") (pinfunction "4_4") (pintype "passive"))
    )
    (net (code "51") (name "Net-(D13-PadA)") (class "Default")
      (node (ref "D13") (pin "A") (pinfunction "A_A") (pintype "passive"))
      (node (ref "JP1") (pin "19") (pinfunction "19_19") (pintype "passive"))
    )
    (net (code "52") (name "Net-(J1-Pad2)") (class "Default")
      (node (ref "J1") (pin "2") (pinfunction "2_2") (pintype "bidirectional"))
      (node (ref "R24") (pin "1") (pinfunction "1_1") (pintype "passive"))
    )
    (net (code "53") (name "Net-(J1-Pad3)") (class "Default")
      (node (ref "J1") (pin "3") (pinfunction "3_3") (pintype "bidirectional"))
      (node (ref "R23") (pin "1") (pinfunction "1_1") (pintype "passive"))
    )
    (net (code "54") (name "Net-(J2-PadP1)") (class "Default")
      (node (ref "J2") (pin "P1") (pinfunction "P1_P1") (pintype "bidirectional"))
      (node (ref "R2") (pin "2") (pinfunction "2_2") (pintype "passive"))
    )
    (net (code "55") (name "Net-(J3-PadP1)") (class "Default")
      (node (ref "J3") (pin "P1") (pinfunction "P1_P1") (pintype "bidirectional"))
      (node (ref "R5") (pin "2") (pinfunction "2_2") (pintype "passive"))
    )
    (net (code "56") (name "Net-(J4-PadP1)") (class "Default")
      (node (ref "J4") (pin "P1") (pinfunction "P1_P1") (pintype "bidirectional"))
      (node (ref "R8") (pin "2") (pinfunction "2_2") (pintype "passive"))
    )
    (net (code "57") (name "Net-(J5-PadP1)") (class "Default")
      (node (ref "J5") (pin "P1") (pinfunction "P1_P1") (pintype "bidirectional"))
      (node (ref "R11") (pin "2") (pinfunction "2_2") (pintype "passive"))
    )
    (net (code "58") (name "Net-(J6-VDD)") (class "Default")
      (node (ref "C20") (pin "2") (pinfunction "2_2") (pintype "passive"))
      (node (ref "J6") (pin "4") (pinfunction "VDD_4") (pintype "bidirectional"))
      (node (ref "R27") (pin "2") (pinfunction "2_2") (pintype "passive"))
      (node (ref "U3") (pin "5") (pinfunction "OUT_5") (pintype "bidirectional"))
    )
    (net (code "59") (name "Net-(Q1-2)") (class "Default")
      (node (ref "C5") (pin "1") (pinfunction "1_1") (pintype "passive"))
      (node (ref "Q1") (pin "3") (pinfunction "2_3") (pintype "passive"))
      (node (ref "U1") (pin "32") (pinfunction "PTA18/EXTAL0/FTM0_FLT2/FTM_CLKIN0_32") (pintype "bidirectional"))
    )
    (net (code "60") (name "Net-(Q2-2)") (class "Default")
      (node (ref "C12") (pin "1") (pinfunction "1_1") (pintype "passive"))
      (node (ref "Q2") (pin "3") (pinfunction "2_3") (pintype "passive"))
      (node (ref "R14") (pin "2") (pinfunction "2_2") (pintype "passive"))
      (node (ref "U2") (pin "21") (pinfunction "OSC1/CLKIN_21") (pintype "bidirectional"))
    )
    (net (code "61") (name "Net-(Q3-2)") (class "Default")
      (node (ref "C14") (pin "1") (pinfunction "1_1") (pintype "passive"))
      (node (ref "Q3") (pin "4") (pinfunction "2_4") (pintype "passive"))
      (node (ref "U1") (pin "19") (pinfunction "XTAL32_19") (pintype "passive"))
    )
    (net (code "62") (name "Net-(U1-EXTAL32)") (class "Default")
      (node (ref "C13") (pin "1") (pinfunction "1_1") (pintype "passive"))
      (node (ref "Q3") (pin "1") (pinfunction "1_1") (pintype "passive"))
      (node (ref "U1") (pin "20") (pinfunction "EXTAL32_20") (pintype "passive"))
    )
    (net (code "63") (name "Net-(U1-PTA19{slash}XTAL0{slash}FTM1_FLT0{slash}FTM_CLKIN1{slash}LPTMR0_ALT1)") (class "Default")
      (node (ref "C6") (pin "1") (pinfunction "1_1") (pintype "passive"))
      (node (ref "Q1") (pin "1") (pinfunction "1_1") (pintype "passive"))
      (node (ref "U1") (pin "33") (pinfunction "PTA19/XTAL0/FTM1_FLT0/FTM_CLKIN1/LPTMR0_ALT1_33") (pintype "bidirectional"))
    )
    (net (code "64") (name "Net-(U1-VREF_OUT{slash}CMP1_IN5{slash}CMP0_IN5{slash}ADC1_SE18)") (class "Default")
      (node (ref "C19") (pin "2") (pinfunction "2_2") (pintype "passive"))
      (node (ref "U1") (pin "17") (pinfunction "VREF_OUT/CMP1_IN5/CMP0_IN5/ADC1_SE18_17") (pintype "bidirectional"))
    )
    (net (code "65") (name "Net-(U2--CS)") (class "Default")
      (node (ref "R15") (pin "1") (pinfunction "1_1") (pintype "passive"))
      (node (ref "U2") (pin "23") (pinfunction "-CS_23") (pintype "bidirectional"))
    )
    (net (code "66") (name "Net-(U2--DR)") (class "Default")
      (node (ref "R19") (pin "1") (pinfunction "1_1") (pintype "passive"))
      (node (ref "U2") (pin "18") (pinfunction "-DR_18") (pintype "bidirectional"))
    )
    (net (code "67") (name "Net-(U2--RESET)") (class "Default")
      (node (ref "R20") (pin "1") (pinfunction "1_1") (pintype "passive"))
      (node (ref "U2") (pin "27") (pinfunction "-RESET_27") (pintype "bidirectional"))
    )
    (net (code "68") (name "Net-(U2-AVDD)") (class "Default")
      (node (ref "C17") (pin "1") (pinfunction "1_1") (pintype "passive"))
      (node (ref "R22") (pin "1") (pinfunction "1_1") (pintype "passive"))
      (node (ref "U2") (pin "1") (pinfunction "AVDD_1") (pintype "bidirectional"))
    )
    (net (code "69") (name "Net-(U2-DVDD)") (class "Default")
      (node (ref "C15") (pin "1") (pinfunction "1_1") (pintype "passive"))
      (node (ref "R21") (pin "1") (pinfunction "1_1") (pintype "passive"))
      (node (ref "U2") (pin "28") (pinfunction "DVDD_28") (pintype "bidirectional"))
    )
    (net (code "70") (name "Net-(U2-OSC2)") (class "Default")
      (node (ref "C11") (pin "1") (pinfunction "1_1") (pintype "passive"))
      (node (ref "Q2") (pin "1") (pinfunction "1_1") (pintype "passive"))
      (node (ref "R14") (pin "1") (pinfunction "1_1") (pintype "passive"))
      (node (ref "U2") (pin "22") (pinfunction "OSC2_22") (pintype "bidirectional"))
    )
    (net (code "71") (name "Net-(U2-REFIN+{slash}OUT)") (class "Default")
      (node (ref "C16") (pin "1") (pinfunction "1_1") (pintype "passive"))
      (node (ref "U2") (pin "14") (pinfunction "REFIN+/OUT_14") (pintype "bidirectional"))
    )
    (net (code "72") (name "Net-(U2-SCK)") (class "Default")
      (node (ref "R16") (pin "1") (pinfunction "1_1") (pintype "passive"))
      (node (ref "U2") (pin "24") (pinfunction "SCK_24") (pintype "bidirectional"))
    )
    (net (code "73") (name "Net-(U2-SDI)") (class "Default")
      (node (ref "R18") (pin "1") (pinfunction "1_1") (pintype "passive"))
      (node (ref "U2") (pin "26") (pinfunction "SDI_26") (pintype "bidirectional"))
    )
    (net (code "74") (name "Net-(U2-SDO)") (class "Default")
      (node (ref "R17") (pin "1") (pinfunction "1_1") (pintype "passive"))
      (node (ref "U2") (pin "25") (pinfunction "SDO_25") (pintype "bidirectional"))
    )
    (net (code "75") (name "unconnected-(J1-Pad4)") (class "Default")
      (node (ref "J1") (pin "4") (pinfunction "4_4") (pintype "bidirectional"))
    )
    (net (code "76") (name "unconnected-(J6-DAT1{slash}NC-Pad8)") (class "Default")
      (node (ref "J6") (pin "8") (pinfunction "DAT1/NC_8") (pintype "bidirectional"))
    )
    (net (code "77") (name "unconnected-(J6-DAT2{slash}NC-Pad1)") (class "Default")
      (node (ref "J6") (pin "1") (pinfunction "DAT2/NC_1") (pintype "bidirectional"))
    )
    (net (code "78") (name "unconnected-(JP1-Pad2)") (class "Default")
      (node (ref "JP1") (pin "2") (pinfunction "2_2") (pintype "passive"))
    )
    (net (code "79") (name "unconnected-(JP1-Pad3)") (class "Default")
      (node (ref "JP1") (pin "3") (pinfunction "3_3") (pintype "passive"))
    )
    (net (code "80") (name "unconnected-(JP1-Pad14)") (class "Default")
      (node (ref "JP1") (pin "14") (pinfunction "14_14") (pintype "passive"))
    )
    (net (code "81") (name "unconnected-(JP1-Pad16)") (class "Default")
      (node (ref "JP1") (pin "16") (pinfunction "16_16") (pintype "passive"))
    )
    (net (code "82") (name "unconnected-(JP1-Pad17)") (class "Default")
      (node (ref "JP1") (pin "17") (pinfunction "17_17") (pintype "passive"))
    )
    (net (code "83") (name "unconnected-(JP1-Pad18)") (class "Default")
      (node (ref "JP1") (pin "18") (pinfunction "18_18") (pintype "passive"))
    )
    (net (code "84") (name "unconnected-(JP1-Pad20)") (class "Default")
      (node (ref "JP1") (pin "20") (pinfunction "20_20") (pintype "passive"))
    )
    (net (code "85") (name "unconnected-(JP2-Pad1)") (class "Default")
      (node (ref "JP2") (pin "1") (pinfunction "1_1") (pintype "passive"))
    )
    (net (code "86") (name "unconnected-(JP2-Pad3)") (class "Default")
      (node (ref "JP2") (pin "3") (pinfunction "3_3") (pintype "passive"))
    )
    (net (code "87") (name "unconnected-(JP2-Pad5)") (class "Default")
      (node (ref "JP2") (pin "5") (pinfunction "5_5") (pintype "passive"))
    )
    (net (code "88") (name "unconnected-(JP2-Pad7)") (class "Default")
      (node (ref "JP2") (pin "7") (pinfunction "7_7") (pintype "passive"))
    )
    (net (code "89") (name "unconnected-(JP2-Pad11)") (class "Default")
      (node (ref "JP2") (pin "11") (pinfunction "11_11") (pintype "passive"))
    )
    (net (code "90") (name "unconnected-(JP2-Pad12)") (class "Default")
      (node (ref "JP2") (pin "12") (pinfunction "12_12") (pintype "passive"))
    )
    (net (code "91") (name "unconnected-(JP2-Pad13)") (class "Default")
      (node (ref "JP2") (pin "13") (pinfunction "13_13") (pintype "passive"))
    )
    (net (code "92") (name "unconnected-(JP2-Pad15)") (class "Default")
      (node (ref "JP2") (pin "15") (pinfunction "15_15") (pintype "passive"))
    )
    (net (code "93") (name "unconnected-(JP2-Pad16)") (class "Default")
      (node (ref "JP2") (pin "16") (pinfunction "16_16") (pintype "passive"))
    )
    (net (code "94") (name "unconnected-(JP2-Pad17)") (class "Default")
      (node (ref "JP2") (pin "17") (pinfunction "17_17") (pintype "passive"))
    )
    (net (code "95") (name "unconnected-(JP2-Pad18)") (class "Default")
      (node (ref "JP2") (pin "18") (pinfunction "18_18") (pintype "passive"))
    )
    (net (code "96") (name "unconnected-(JP2-Pad19)") (class "Default")
      (node (ref "JP2") (pin "19") (pinfunction "19_19") (pintype "passive"))
    )
    (net (code "97") (name "unconnected-(JP2-Pad21)") (class "Default")
      (node (ref "JP2") (pin "21") (pinfunction "21_21") (pintype "passive"))
    )
    (net (code "98") (name "unconnected-(JP2-Pad22)") (class "Default")
      (node (ref "JP2") (pin "22") (pinfunction "22_22") (pintype "passive"))
    )
    (net (code "99") (name "unconnected-(JP2-Pad23)") (class "Default")
      (node (ref "JP2") (pin "23") (pinfunction "23_23") (pintype "passive"))
    )
    (net (code "100") (name "unconnected-(JP2-Pad24)") (class "Default")
      (node (ref "JP2") (pin "24") (pinfunction "24_24") (pintype "passive"))
    )
    (net (code "101") (name "unconnected-(JP2-Pad26)") (class "Default")
      (node (ref "JP2") (pin "26") (pinfunction "26_26") (pintype "passive"))
    )
    (net (code "102") (name "unconnected-(JP2-Pad27)") (class "Default")
      (node (ref "JP2") (pin "27") (pinfunction "27_27") (pintype "passive"))
    )
    (net (code "103") (name "unconnected-(JP2-Pad28)") (class "Default")
      (node (ref "JP2") (pin "28") (pinfunction "28_28") (pintype "passive"))
    )
    (net (code "104") (name "unconnected-(JP2-Pad29)") (class "Default")
      (node (ref "JP2") (pin "29") (pinfunction "29_29") (pintype "passive"))
    )
    (net (code "105") (name "unconnected-(JP2-Pad30)") (class "Default")
      (node (ref "JP2") (pin "30") (pinfunction "30_30") (pintype "passive"))
    )
    (net (code "106") (name "unconnected-(JP2-Pad31)") (class "Default")
      (node (ref "JP2") (pin "31") (pinfunction "31_31") (pintype "passive"))
    )
    (net (code "107") (name "unconnected-(JP2-Pad32)") (class "Default")
      (node (ref "JP2") (pin "32") (pinfunction "32_32") (pintype "passive"))
    )
    (net (code "108") (name "unconnected-(JP2-Pad33)") (class "Default")
      (node (ref "JP2") (pin "33") (pinfunction "33_33") (pintype "passive"))
    )
    (net (code "109") (name "unconnected-(JP2-Pad35)") (class "Default")
      (node (ref "JP2") (pin "35") (pinfunction "35_35") (pintype "passive"))
    )
    (net (code "110") (name "unconnected-(JP2-Pad36)") (class "Default")
      (node (ref "JP2") (pin "36") (pinfunction "36_36") (pintype "passive"))
    )
    (net (code "111") (name "unconnected-(JP2-Pad37)") (class "Default")
      (node (ref "JP2") (pin "37") (pinfunction "37_37") (pintype "passive"))
    )
    (net (code "112") (name "unconnected-(JP2-Pad38)") (class "Default")
      (node (ref "JP2") (pin "38") (pinfunction "38_38") (pintype "passive"))
    )
    (net (code "113") (name "unconnected-(JP2-Pad40)") (class "Default")
      (node (ref "JP2") (pin "40") (pinfunction "40_40") (pintype "passive"))
    )
    (net (code "114") (name "unconnected-(U1-ADC0_DM0{slash}ADC1_DM3-Pad10)") (class "Default")
      (node (ref "U1") (pin "10") (pinfunction "ADC0_DM0/ADC1_DM3_10") (pintype "bidirectional"))
    )
    (net (code "115") (name "unconnected-(U1-ADC0_DP0{slash}ADC1_DP3-Pad9)") (class "Default")
      (node (ref "U1") (pin "9") (pinfunction "ADC0_DP0/ADC1_DP3_9") (pintype "bidirectional"))
    )
    (net (code "116") (name "unconnected-(U1-ADC1_DM0{slash}ADC0_DM3-Pad12)") (class "Default")
      (node (ref "U1") (pin "12") (pinfunction "ADC1_DM0/ADC0_DM3_12") (pintype "bidirectional"))
    )
    (net (code "117") (name "unconnected-(U1-ADC1_DP0{slash}ADC0_DP3-Pad11)") (class "Default")
      (node (ref "U1") (pin "11") (pinfunction "ADC1_DP0/ADC0_DP3_11") (pintype "bidirectional"))
    )
    (net (code "118") (name "unconnected-(U1-DAC0_OUT{slash}CMP1_IN3{slash}ADC0_SE23-Pad18)") (class "Default")
      (node (ref "U1") (pin "18") (pinfunction "DAC0_OUT/CMP1_IN3/ADC0_SE23_18") (pintype "bidirectional"))
    )
    (net (code "119") (name "unconnected-(U1-PTA4{slash}LLWU_P3{slash}NMI{slash}EZP_CS{slash}FTM0_CH1-Pad26)") (class "Default")
      (node (ref "U1") (pin "26") (pinfunction "PTA4/LLWU_P3/NMI/EZP_CS/FTM0_CH1_26") (pintype "bidirectional"))
    )
    (net (code "120") (name "unconnected-(U1-PTA5{slash}USB_CLKIN{slash}FTM0_CH2{slash}I2S0_TX_BCLK{slash}JTAG_TRST-Pad27)") (class "Default")
      (node (ref "U1") (pin "27") (pinfunction "PTA5/USB_CLKIN/FTM0_CH2/I2S0_TX_BCLK/JTAG_TRST_27") (pintype "bidirectional"))
    )
    (net (code "121") (name "unconnected-(U1-PTA12{slash}FTM1_CH0{slash}I2S0_TXD0{slash}FTM1_QD_PHA-Pad28)") (class "Default")
      (node (ref "U1") (pin "28") (pinfunction "PTA12/FTM1_CH0/I2S0_TXD0/FTM1_QD_PHA_28") (pintype "bidirectional"))
    )
    (net (code "122") (name "unconnected-(U1-PTA13{slash}LLWU_P4{slash}FTM1_CH1{slash}I2S0_TX_FS{slash}FTM1_QD_PHB-Pad29)") (class "Default")
      (node (ref "U1") (pin "29") (pinfunction "PTA13/LLWU_P4/FTM1_CH1/I2S0_TX_FS/FTM1_QD_PHB_29") (pintype "bidirectional"))
    )
    (net (code "123") (name "unconnected-(U1-PTB3{slash}ADC0_SE13{slash}I2C0_SDA{slash}UART0_CTS{slash}FTM0_FLT0-Pad38)") (class "Default")
      (node (ref "U1") (pin "38") (pinfunction "PTB3/ADC0_SE13/I2C0_SDA/UART0_CTS/FTM0_FLT0_38") (pintype "bidirectional"))
    )
    (net (code "124") (name "unconnected-(U1-PTB16{slash}SPI1_SOUT{slash}UART0_RX{slash}FTM_CLKIN0{slash}FB_AD17{slash}EWM_IN-Pad39)") (class "Default")
      (node (ref "U1") (pin "39") (pinfunction "PTB16/SPI1_SOUT/UART0_RX/FTM_CLKIN0/FB_AD17/EWM_IN_39") (pintype "bidirectional"))
    )
    (net (code "125") (name "unconnected-(U1-PTB17{slash}SPI1_SIN{slash}UART0_TX{slash}FTM-CLKIN1{slash}FB_AD16{slash}EWM_OUT-Pad40)") (class "Default")
      (node (ref "U1") (pin "40") (pinfunction "PTB17/SPI1_SIN/UART0_TX/FTM-CLKIN1/FB_AD16/EWM_OUT_40") (pintype "bidirectional"))
    )
    (net (code "126") (name "unconnected-(U1-PTB18{slash}FTM2_CH0{slash}I2S0_TX_BCLKD{slash}FB_AD15{slash}FTM2_QD_PHA-Pad41)") (class "Default")
      (node (ref "U1") (pin "41") (pinfunction "PTB18/FTM2_CH0/I2S0_TX_BCLKD/FB_AD15/FTM2_QD_PHA_41") (pintype "bidirectional"))
    )
    (net (code "127") (name "unconnected-(U1-PTB19{slash}FTM2_CH1{slash}I2S0_TX_FS{slash}FB_OE{slash}FTM2_QD_PHB-Pad42)") (class "Default")
      (node (ref "U1") (pin "42") (pinfunction "PTB19/FTM2_CH1/I2S0_TX_FS/FB_OE/FTM2_QD_PHB_42") (pintype "bidirectional"))
    )
    (net (code "128") (name "unconnected-(U1-PTC0{slash}ADC0_SE14{slash}SPI0_PCS4{slash}PDB0_EXTRG{slash}USB_SOF_OUT{slash}FB_AD14-Pad43)") (class "Default")
      (node (ref "U1") (pin "43") (pinfunction "PTC0/ADC0_SE14/SPI0_PCS4/PDB0_EXTRG/USB_SOF_OUT/FB_AD14_43") (pintype "bidirectional"))
    )
    (net (code "129") (name "unconnected-(U1-PTC2{slash}ADC0_SE4B{slash}CMP1_IN0{slash}SPI_PCS2{slash}UART1_CTS{slash}FTM0_CH1{slash}FB_AD12{slash}I2S0_TX_FS{slash}LPUART0_CTS-Pad45)") (class "Default")
      (node (ref "U1") (pin "45") (pinfunction "PTC2/ADC0_SE4B/CMP1_IN0/SPI_PCS2/UART1_CTS/FTM0_CH1/FB_AD12/I2S0_TX_FS/LPUART0_CTS_45") (pintype "bidirectional"))
    )
    (net (code "130") (name "unconnected-(U1-PTC3{slash}LLWU_P7{slash}CMP1_IN1{slash}SPI0_PCS1{slash}UART1_RX{slash}FTM0-CH2{slash}CLKOUT{slash}I2S0_TX_BCLK{slash}LPUART0_RX-Pad46)") (class "Default")
      (node (ref "U1") (pin "46") (pinfunction "PTC3/LLWU_P7/CMP1_IN1/SPI0_PCS1/UART1_RX/FTM0-CH2/CLKOUT/I2S0_TX_BCLK/LPUART0_RX_46") (pintype "bidirectional"))
    )
    (net (code "131") (name "unconnected-(U1-PTD0{slash}LLWU_P12{slash}SPI0_PCS0{slash}UART2-RTS{slash}FTM3_CH0{slash}FB_ALE{slash}FB_CS1{slash}FB_TS{slash}LPUART0_RTS-Pad57)") (class "Default")
      (node (ref "U1") (pin "57") (pinfunction "PTD0/LLWU_P12/SPI0_PCS0/UART2-RTS/FTM3_CH0/FB_ALE/FB_CS1/FB_TS/LPUART0_RTS_57") (pintype "bidirectional"))
    )
    (net (code "132") (name "unconnected-(U1-PTD1{slash}ADC0_SE5B{slash}SPI0_SCK{slash}UART2-CTS{slash}FTM3_CH1{slash}FB_CS0{slash}LPUART0_CTS-Pad58)") (class "Default")
      (node (ref "U1") (pin "58") (pinfunction "PTD1/ADC0_SE5B/SPI0_SCK/UART2-CTS/FTM3_CH1/FB_CS0/LPUART0_CTS_58") (pintype "bidirectional"))
    )
    (net (code "133") (name "unconnected-(U1-PTD2{slash}LLWU_P13{slash}SPI0_SOUT{slash}UART2_RX{slash}FTM3_CH2{slash}FB_AD4{slash}LPUART0_RX{slash}I2C0_SCL-Pad59)") (class "Default")
      (node (ref "U1") (pin "59") (pinfunction "PTD2/LLWU_P13/SPI0_SOUT/UART2_RX/FTM3_CH2/FB_AD4/LPUART0_RX/I2C0_SCL_59") (pintype "bidirectional"))
    )
    (net (code "134") (name "unconnected-(U3-PWRGD-Pad4)") (class "Default")
      (node (ref "U3") (pin "4") (pinfunction "PWRGD_4") (pintype "bidirectional"))
    )
    (net (code "135") (name "unconnected-(U4-PWRGD-Pad4)") (class "Default")
      (node (ref "U4") (pin "4") (pinfunction "PWRGD_4") (pintype "bidirectional"))
    )
    (net (code "136") (name "unconnected-(U5-PWRGD-Pad4)") (class "Default")
      (node (ref "U5") (pin "4") (pinfunction "PWRGD_4") (pintype "bidirectional"))
    )
    (net (code "137") (name "unconnected-(U6-AUX-Pad12)") (class "Default")
      (node (ref "U6") (pin "12") (pinfunction "AUX_12") (pintype "bidirectional"))
    )
    (net (code "138") (name "unconnected-(U6-VMUX-Pad11)") (class "Default")
      (node (ref "U6") (pin "11") (pinfunction "VMUX_11") (pintype "bidirectional"))
    )
  )
)
